# watering_uzin.net
KiCad netlist of a schematic drawn in EAGLE
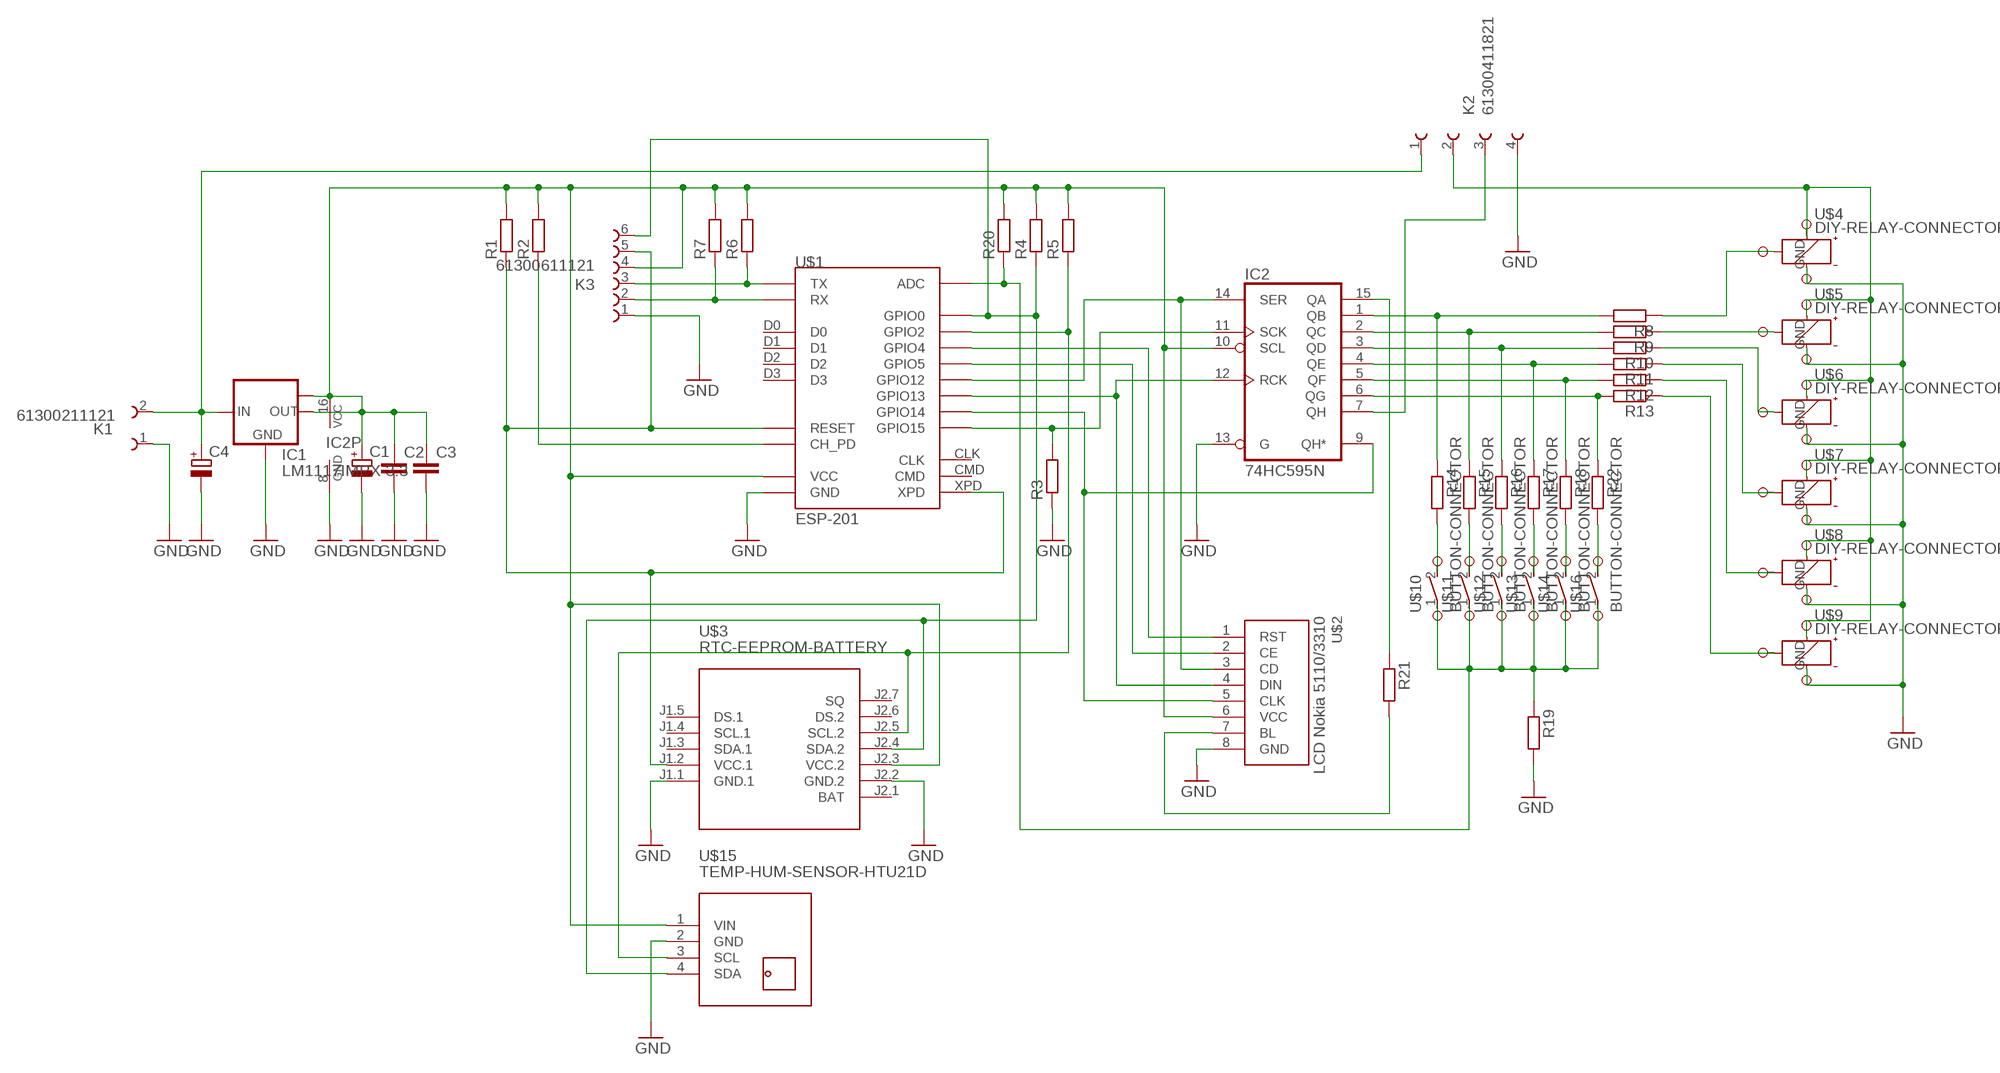
[diagram p0: schematic, sheet 1]

(export (version "E")
  (design (tool "Eeschema 10.0.6"))
  (components
    (comp (ref "C1")
      (value "CPOL-EUSANYO_F13")
      (footprint "eagle-import:SANYO-OSCON_F13")
      (libsource (lib "eagle-import") (part "CPOL-EUSANYO_F13"))
    )
    (comp (ref "C2")
      (value "C-EUC1210")
      (footprint "eagle-import:C1210")
      (libsource (lib "eagle-import") (part "C-EUC1210"))
    )
    (comp (ref "C3")
      (value "C-EUC1210")
      (footprint "eagle-import:C1210")
      (libsource (lib "eagle-import") (part "C-EUC1210"))
    )
    (comp (ref "C4")
      (value "CPOL-EUSANYO_F13")
      (footprint "eagle-import:SANYO-OSCON_F13")
      (libsource (lib "eagle-import") (part "CPOL-EUSANYO_F13"))
    )
    (comp (ref "IC1")
      (value "LM1117IMPX-3.3")
      (footprint "eagle-import:SOT223")
      (libsource (lib "eagle-import") (part "LM1117IMPX-3.3"))
    )
    (comp (ref "IC2")
      (value "74HC595N")
      (footprint "eagle-import:DIL16")
      (libsource (lib "eagle-import") (part "74595NHC"))
    )
    (comp (ref "K1")
      (value "61300211121")
      (footprint "eagle-import:61300211121")
      (libsource (lib "eagle-import") (part "61300211121"))
    )
    (comp (ref "K2")
      (value "61300411821")
      (footprint "eagle-import:61300411821")
      (libsource (lib "eagle-import") (part "61300411821"))
    )
    (comp (ref "K3")
      (value "61300611121")
      (footprint "eagle-import:61300611121")
      (libsource (lib "eagle-import") (part "61300611121"))
    )
    (comp (ref "R1")
      (value "R-EU_R0805")
      (footprint "eagle-import:R0805")
      (libsource (lib "eagle-import") (part "R-EU_R0805"))
    )
    (comp (ref "R2")
      (value "R-EU_R0805")
      (footprint "eagle-import:R0805")
      (libsource (lib "eagle-import") (part "R-EU_R0805"))
    )
    (comp (ref "R3")
      (value "R-EU_R0805")
      (footprint "eagle-import:R0805")
      (libsource (lib "eagle-import") (part "R-EU_R0805"))
    )
    (comp (ref "R4")
      (value "R-EU_R0805")
      (footprint "eagle-import:R0805")
      (libsource (lib "eagle-import") (part "R-EU_R0805"))
    )
    (comp (ref "R5")
      (value "R-EU_R0805")
      (footprint "eagle-import:R0805")
      (libsource (lib "eagle-import") (part "R-EU_R0805"))
    )
    (comp (ref "R6")
      (value "R-EU_R0805")
      (footprint "eagle-import:R0805")
      (libsource (lib "eagle-import") (part "R-EU_R0805"))
    )
    (comp (ref "R7")
      (value "R-EU_R0805")
      (footprint "eagle-import:R0805")
      (libsource (lib "eagle-import") (part "R-EU_R0805"))
    )
    (comp (ref "R8")
      (value "R-EU_R0805")
      (footprint "eagle-import:R0805")
      (libsource (lib "eagle-import") (part "R-EU_R0805"))
    )
    (comp (ref "R9")
      (value "R-EU_R0805")
      (footprint "eagle-import:R0805")
      (libsource (lib "eagle-import") (part "R-EU_R0805"))
    )
    (comp (ref "R10")
      (value "R-EU_R0805")
      (footprint "eagle-import:R0805")
      (libsource (lib "eagle-import") (part "R-EU_R0805"))
    )
    (comp (ref "R11")
      (value "R-EU_R0805")
      (footprint "eagle-import:R0805")
      (libsource (lib "eagle-import") (part "R-EU_R0805"))
    )
    (comp (ref "R12")
      (value "R-EU_R0805")
      (footprint "eagle-import:R0805")
      (libsource (lib "eagle-import") (part "R-EU_R0805"))
    )
    (comp (ref "R13")
      (value "R-EU_R0805")
      (footprint "eagle-import:R0805")
      (libsource (lib "eagle-import") (part "R-EU_R0805"))
    )
    (comp (ref "R14")
      (value "R-EU_R0805")
      (footprint "eagle-import:R0805")
      (libsource (lib "eagle-import") (part "R-EU_R0805"))
    )
    (comp (ref "R15")
      (value "R-EU_R0805")
      (footprint "eagle-import:R0805")
      (libsource (lib "eagle-import") (part "R-EU_R0805"))
    )
    (comp (ref "R16")
      (value "R-EU_R0805")
      (footprint "eagle-import:R0805")
      (libsource (lib "eagle-import") (part "R-EU_R0805"))
    )
    (comp (ref "R17")
      (value "R-EU_R0805")
      (footprint "eagle-import:R0805")
      (libsource (lib "eagle-import") (part "R-EU_R0805"))
    )
    (comp (ref "R18")
      (value "R-EU_R0805")
      (footprint "eagle-import:R0805")
      (libsource (lib "eagle-import") (part "R-EU_R0805"))
    )
    (comp (ref "R19")
      (value "R-EU_R0805")
      (footprint "eagle-import:R0805")
      (libsource (lib "eagle-import") (part "R-EU_R0805"))
    )
    (comp (ref "R20")
      (value "R-EU_R0805")
      (footprint "eagle-import:R0805")
      (libsource (lib "eagle-import") (part "R-EU_R0805"))
    )
    (comp (ref "R21")
      (value "R-EU_R0805")
      (footprint "eagle-import:R0805")
      (libsource (lib "eagle-import") (part "R-EU_R0805"))
    )
    (comp (ref "R22")
      (value "R-EU_R0805")
      (footprint "eagle-import:R0805")
      (libsource (lib "eagle-import") (part "R-EU_R0805"))
    )
    (comp (ref "U$1")
      (value "ESP-201")
      (footprint "eagle-import:ESP-201")
      (libsource (lib "eagle-import") (part "ESP-201"))
    )
    (comp (ref "U$2")
      (value "NOKIA5110")
      (footprint "eagle-import:NOKIA5110")
      (libsource (lib "eagle-import") (part "NOKIA5110"))
    )
    (comp (ref "U$3")
      (value "RTC-EEPROM-BATTERY")
      (footprint "eagle-import:RTC-EEPROM-BATTERY")
      (libsource (lib "eagle-import") (part "RTC-EEPROM-BATTERY"))
    )
    (comp (ref "U$4")
      (value "DIY-RELAY-CONNECTOR")
      (footprint "eagle-import:DIY-RELAY-CONNECTOR")
      (libsource (lib "eagle-import") (part "DIY-RELAY-CONNECTOR"))
    )
    (comp (ref "U$5")
      (value "DIY-RELAY-CONNECTOR")
      (footprint "eagle-import:DIY-RELAY-CONNECTOR")
      (libsource (lib "eagle-import") (part "DIY-RELAY-CONNECTOR"))
    )
    (comp (ref "U$6")
      (value "DIY-RELAY-CONNECTOR")
      (footprint "eagle-import:DIY-RELAY-CONNECTOR")
      (libsource (lib "eagle-import") (part "DIY-RELAY-CONNECTOR"))
    )
    (comp (ref "U$7")
      (value "DIY-RELAY-CONNECTOR")
      (footprint "eagle-import:DIY-RELAY-CONNECTOR")
      (libsource (lib "eagle-import") (part "DIY-RELAY-CONNECTOR"))
    )
    (comp (ref "U$8")
      (value "DIY-RELAY-CONNECTOR")
      (footprint "eagle-import:DIY-RELAY-CONNECTOR")
      (libsource (lib "eagle-import") (part "DIY-RELAY-CONNECTOR"))
    )
    (comp (ref "U$9")
      (value "DIY-RELAY-CONNECTOR")
      (footprint "eagle-import:DIY-RELAY-CONNECTOR")
      (libsource (lib "eagle-import") (part "DIY-RELAY-CONNECTOR"))
    )
    (comp (ref "U$10")
      (value "BUTTON-CONNECTOR")
      (footprint "eagle-import:BUTTON-CONNECTOR")
      (libsource (lib "eagle-import") (part "BUTTON-CONNECTOR"))
    )
    (comp (ref "U$11")
      (value "BUTTON-CONNECTOR")
      (footprint "eagle-import:BUTTON-CONNECTOR")
      (libsource (lib "eagle-import") (part "BUTTON-CONNECTOR"))
    )
    (comp (ref "U$12")
      (value "BUTTON-CONNECTOR")
      (footprint "eagle-import:BUTTON-CONNECTOR")
      (libsource (lib "eagle-import") (part "BUTTON-CONNECTOR"))
    )
    (comp (ref "U$13")
      (value "BUTTON-CONNECTOR")
      (footprint "eagle-import:BUTTON-CONNECTOR")
      (libsource (lib "eagle-import") (part "BUTTON-CONNECTOR"))
    )
    (comp (ref "U$14")
      (value "BUTTON-CONNECTOR")
      (footprint "eagle-import:BUTTON-CONNECTOR")
      (libsource (lib "eagle-import") (part "BUTTON-CONNECTOR"))
    )
    (comp (ref "U$15")
      (value "TEMP-HUM-SENSOR-HTU21D")
      (footprint "eagle-import:TEMP-HUM-SENSOR-HTU21D")
      (libsource (lib "eagle-import") (part "TEMP-HUM-SENSOR-HTU21D"))
    )
    (comp (ref "U$16")
      (value "BUTTON-CONNECTOR")
      (footprint "eagle-import:BUTTON-CONNECTOR")
      (libsource (lib "eagle-import") (part "BUTTON-CONNECTOR"))
    )
  )
  (nets
    (net (code "1") (name "GND") (class "Default")
      (node (ref "C1") (pin "-") (pinfunction "-_-") (pintype "passive"))
      (node (ref "C2") (pin "2") (pinfunction "2_2") (pintype "passive"))
      (node (ref "C3") (pin "2") (pinfunction "2_2") (pintype "passive"))
      (node (ref "C4") (pin "-") (pinfunction "-_-") (pintype "passive"))
      (node (ref "IC1") (pin "1") (pinfunction "GND_1") (pintype "input"))
      (node (ref "IC2") (pin "13") (pinfunction "G_13") (pintype "input"))
      (node (ref "IC2") (pin "8") (pinfunction "GND_8") (pintype "power_in"))
      (node (ref "K1") (pin "1") (pinfunction "1_1") (pintype "passive"))
      (node (ref "K2") (pin "4") (pinfunction "4_4") (pintype "passive"))
      (node (ref "K3") (pin "1") (pinfunction "1_1") (pintype "passive"))
      (node (ref "R19") (pin "2") (pinfunction "2_2") (pintype "passive"))
      (node (ref "R3") (pin "1") (pinfunction "1_1") (pintype "passive"))
      (node (ref "U$1") (pin "GND") (pinfunction "GND_GND") (pintype "bidirectional"))
      (node (ref "U$1") (pin "GND_2") (pinfunction "GND_GND_2") (pintype "bidirectional"))
      (node (ref "U$1") (pin "GND_3") (pinfunction "GND_GND_3") (pintype "bidirectional"))
      (node (ref "U$15") (pin "2") (pinfunction "GND_2") (pintype "power_in"))
      (node (ref "U$2") (pin "8") (pinfunction "GND_8") (pintype "power_in"))
      (node (ref "U$3") (pin "J1.1") (pinfunction "GND.1_J1.1") (pintype "power_in"))
      (node (ref "U$3") (pin "J2.2") (pinfunction "GND.2_J2.2") (pintype "power_in"))
      (node (ref "U$4") (pin "GND") (pinfunction "GND_GND") (pintype "passive"))
      (node (ref "U$5") (pin "GND") (pinfunction "GND_GND") (pintype "passive"))
      (node (ref "U$6") (pin "GND") (pinfunction "GND_GND") (pintype "passive"))
      (node (ref "U$7") (pin "GND") (pinfunction "GND_GND") (pintype "passive"))
      (node (ref "U$8") (pin "GND") (pinfunction "GND_GND") (pintype "passive"))
      (node (ref "U$9") (pin "GND") (pinfunction "GND_GND") (pintype "passive"))
    )
    (net (code "2") (name "Net-(IC1-IN)") (class "Default")
      (node (ref "C4") (pin "+") (pinfunction "+_+") (pintype "passive"))
      (node (ref "IC1") (pin "3") (pinfunction "IN_3") (pintype "input"))
      (node (ref "K1") (pin "2") (pinfunction "2_2") (pintype "passive"))
      (node (ref "K2") (pin "1") (pinfunction "1_1") (pintype "passive"))
    )
    (net (code "3") (name "Net-(IC1-OUT)") (class "Default")
      (node (ref "C1") (pin "+") (pinfunction "+_+") (pintype "passive"))
      (node (ref "C2") (pin "1") (pinfunction "1_1") (pintype "passive"))
      (node (ref "C3") (pin "1") (pinfunction "1_1") (pintype "passive"))
      (node (ref "IC1") (pin "2") (pinfunction "OUT_2") (pintype "passive"))
      (node (ref "IC1") (pin "TAB") (pinfunction "OUT1_TAB") (pintype "passive"))
      (node (ref "IC2") (pin "10") (pinfunction "SCL_10") (pintype "input"))
      (node (ref "IC2") (pin "16") (pinfunction "VCC_16") (pintype "power_in"))
      (node (ref "K3") (pin "4") (pinfunction "4_4") (pintype "passive"))
      (node (ref "R1") (pin "2") (pinfunction "2_2") (pintype "passive"))
      (node (ref "R2") (pin "2") (pinfunction "2_2") (pintype "passive"))
      (node (ref "R20") (pin "2") (pinfunction "2_2") (pintype "passive"))
      (node (ref "R4") (pin "2") (pinfunction "2_2") (pintype "passive"))
      (node (ref "R5") (pin "2") (pinfunction "2_2") (pintype "passive"))
      (node (ref "R6") (pin "2") (pinfunction "2_2") (pintype "passive"))
      (node (ref "R7") (pin "2") (pinfunction "2_2") (pintype "passive"))
      (node (ref "U$1") (pin "3V3") (pinfunction "VCC_3V3") (pintype "bidirectional"))
      (node (ref "U$1") (pin "3V3_2") (pinfunction "VCC_3V3_2") (pintype "bidirectional"))
      (node (ref "U$1") (pin "3V3_3") (pinfunction "VCC_3V3_3") (pintype "bidirectional"))
      (node (ref "U$15") (pin "1") (pinfunction "VIN_1") (pintype "power_in"))
      (node (ref "U$2") (pin "6") (pinfunction "VCC_6") (pintype "power_in"))
      (node (ref "U$3") (pin "J2.3") (pinfunction "VCC.2_J2.3") (pintype "power_in"))
    )
    (net (code "4") (name "Net-(IC2A-QA)") (class "Default")
      (node (ref "IC2") (pin "15") (pinfunction "QA_15") (pintype "tri_state"))
      (node (ref "R21") (pin "1") (pinfunction "1_1") (pintype "passive"))
    )
    (net (code "5") (name "Net-(IC2A-QB)") (class "Default")
      (node (ref "IC2") (pin "1") (pinfunction "QB_1") (pintype "tri_state"))
      (node (ref "R14") (pin "1") (pinfunction "1_1") (pintype "passive"))
      (node (ref "R8") (pin "2") (pinfunction "2_2") (pintype "passive"))
    )
    (net (code "6") (name "Net-(IC2A-QC)") (class "Default")
      (node (ref "IC2") (pin "2") (pinfunction "QC_2") (pintype "tri_state"))
      (node (ref "R15") (pin "1") (pinfunction "1_1") (pintype "passive"))
      (node (ref "R9") (pin "2") (pinfunction "2_2") (pintype "passive"))
    )
    (net (code "7") (name "Net-(IC2A-QD)") (class "Default")
      (node (ref "IC2") (pin "3") (pinfunction "QD_3") (pintype "tri_state"))
      (node (ref "R10") (pin "2") (pinfunction "2_2") (pintype "passive"))
      (node (ref "R16") (pin "1") (pinfunction "1_1") (pintype "passive"))
    )
    (net (code "8") (name "Net-(IC2A-QE)") (class "Default")
      (node (ref "IC2") (pin "4") (pinfunction "QE_4") (pintype "tri_state"))
      (node (ref "R11") (pin "2") (pinfunction "2_2") (pintype "passive"))
      (node (ref "R17") (pin "1") (pinfunction "1_1") (pintype "passive"))
    )
    (net (code "9") (name "Net-(IC2A-QF)") (class "Default")
      (node (ref "IC2") (pin "5") (pinfunction "QF_5") (pintype "tri_state"))
      (node (ref "R12") (pin "2") (pinfunction "2_2") (pintype "passive"))
      (node (ref "R18") (pin "1") (pinfunction "1_1") (pintype "passive"))
    )
    (net (code "10") (name "Net-(IC2A-QG)") (class "Default")
      (node (ref "IC2") (pin "6") (pinfunction "QG_6") (pintype "tri_state"))
      (node (ref "R13") (pin "2") (pinfunction "2_2") (pintype "passive"))
      (node (ref "R22") (pin "1") (pinfunction "1_1") (pintype "passive"))
    )
    (net (code "11") (name "Net-(IC2A-QH)") (class "Default")
      (node (ref "IC2") (pin "7") (pinfunction "QH_7") (pintype "tri_state"))
      (node (ref "K2") (pin "3") (pinfunction "3_3") (pintype "passive"))
    )
    (net (code "12") (name "Net-(IC2A-QH*)") (class "Default")
      (node (ref "IC2") (pin "9") (pinfunction "QH*_9") (pintype "tri_state"))
      (node (ref "U$1") (pin "GPIO14") (pinfunction "GPIO14_GPIO14") (pintype "bidirectional"))
      (node (ref "U$2") (pin "5") (pinfunction "CLK_5") (pintype "bidirectional"))
    )
    (net (code "13") (name "Net-(IC2A-RCK)") (class "Default")
      (node (ref "IC2") (pin "12") (pinfunction "RCK_12") (pintype "input"))
      (node (ref "U$1") (pin "GPIO13") (pinfunction "GPIO13_GPIO13") (pintype "bidirectional"))
      (node (ref "U$2") (pin "4") (pinfunction "DIN_4") (pintype "bidirectional"))
    )
    (net (code "14") (name "Net-(IC2A-SCK)") (class "Default")
      (node (ref "IC2") (pin "11") (pinfunction "SCK_11") (pintype "input"))
      (node (ref "R3") (pin "2") (pinfunction "2_2") (pintype "passive"))
      (node (ref "U$1") (pin "GPIO15") (pinfunction "GPIO15_GPIO15") (pintype "bidirectional"))
    )
    (net (code "15") (name "Net-(IC2A-SER)") (class "Default")
      (node (ref "IC2") (pin "14") (pinfunction "SER_14") (pintype "input"))
      (node (ref "U$1") (pin "GPIO12") (pinfunction "GPIO12_GPIO12") (pintype "bidirectional"))
      (node (ref "U$2") (pin "3") (pinfunction "CD_3") (pintype "bidirectional"))
    )
    (net (code "16") (name "Net-(K2-Pad2)") (class "Default")
      (node (ref "K2") (pin "2") (pinfunction "2_2") (pintype "passive"))
      (node (ref "U$4") (pin "VCC") (pinfunction "VCC_VCC") (pintype "passive"))
      (node (ref "U$5") (pin "VCC") (pinfunction "VCC_VCC") (pintype "passive"))
      (node (ref "U$6") (pin "VCC") (pinfunction "VCC_VCC") (pintype "passive"))
      (node (ref "U$7") (pin "VCC") (pinfunction "VCC_VCC") (pintype "passive"))
      (node (ref "U$8") (pin "VCC") (pinfunction "VCC_VCC") (pintype "passive"))
      (node (ref "U$9") (pin "VCC") (pinfunction "VCC_VCC") (pintype "passive"))
    )
    (net (code "17") (name "Net-(K3-Pad2)") (class "Default")
      (node (ref "K3") (pin "2") (pinfunction "2_2") (pintype "passive"))
      (node (ref "R7") (pin "1") (pinfunction "1_1") (pintype "passive"))
      (node (ref "U$1") (pin "RX") (pinfunction "RX_RX") (pintype "bidirectional"))
    )
    (net (code "18") (name "Net-(K3-Pad3)") (class "Default")
      (node (ref "K3") (pin "3") (pinfunction "3_3") (pintype "passive"))
      (node (ref "R6") (pin "1") (pinfunction "1_1") (pintype "passive"))
      (node (ref "U$1") (pin "TX") (pinfunction "TX_TX") (pintype "bidirectional"))
    )
    (net (code "19") (name "Net-(R2-Pad1)") (class "Default")
      (node (ref "R2") (pin "1") (pinfunction "1_1") (pintype "passive"))
      (node (ref "U$1") (pin "CH_PD") (pinfunction "CH_PD_CH_PD") (pintype "bidirectional"))
    )
    (net (code "20") (name "Net-(R8-Pad1)") (class "Default")
      (node (ref "R8") (pin "1") (pinfunction "1_1") (pintype "passive"))
      (node (ref "U$4") (pin "IN") (pinfunction "IN_IN") (pintype "passive"))
    )
    (net (code "21") (name "Net-(R9-Pad1)") (class "Default")
      (node (ref "R9") (pin "1") (pinfunction "1_1") (pintype "passive"))
      (node (ref "U$5") (pin "IN") (pinfunction "IN_IN") (pintype "passive"))
    )
    (net (code "22") (name "Net-(R10-Pad1)") (class "Default")
      (node (ref "R10") (pin "1") (pinfunction "1_1") (pintype "passive"))
      (node (ref "U$6") (pin "IN") (pinfunction "IN_IN") (pintype "passive"))
    )
    (net (code "23") (name "Net-(R11-Pad1)") (class "Default")
      (node (ref "R11") (pin "1") (pinfunction "1_1") (pintype "passive"))
      (node (ref "U$7") (pin "IN") (pinfunction "IN_IN") (pintype "passive"))
    )
    (net (code "24") (name "Net-(R12-Pad1)") (class "Default")
      (node (ref "R12") (pin "1") (pinfunction "1_1") (pintype "passive"))
      (node (ref "U$8") (pin "IN") (pinfunction "IN_IN") (pintype "passive"))
    )
    (net (code "25") (name "Net-(R13-Pad1)") (class "Default")
      (node (ref "R13") (pin "1") (pinfunction "1_1") (pintype "passive"))
      (node (ref "U$9") (pin "IN") (pinfunction "IN_IN") (pintype "passive"))
    )
    (net (code "26") (name "Net-(U$1-RESET)") (class "Default")
      (node (ref "K3") (pin "5") (pinfunction "5_5") (pintype "passive"))
      (node (ref "R1") (pin "1") (pinfunction "1_1") (pintype "passive"))
      (node (ref "U$1") (pin "RST") (pinfunction "RESET_RST") (pintype "bidirectional"))
      (node (ref "U$1") (pin "XPD") (pinfunction "XPD_XPD") (pintype "bidirectional"))
      (node (ref "U$3") (pin "J1.2") (pinfunction "VCC.1_J1.2") (pintype "power_in"))
    )
    (net (code "27") (name "Net-(U$2-BL)") (class "Default")
      (node (ref "R21") (pin "2") (pinfunction "2_2") (pintype "passive"))
      (node (ref "U$2") (pin "7") (pinfunction "BL_7") (pintype "bidirectional"))
    )
    (net (code "28") (name "Net-(U$2-CE)") (class "Default")
      (node (ref "U$1") (pin "GPIO5") (pinfunction "GPIO5_GPIO5") (pintype "bidirectional"))
      (node (ref "U$2") (pin "2") (pinfunction "CE_2") (pintype "bidirectional"))
    )
    (net (code "29") (name "Net-(U$2-RST)") (class "Default")
      (node (ref "U$1") (pin "GPIO4") (pinfunction "GPIO4_GPIO4") (pintype "bidirectional"))
      (node (ref "U$2") (pin "1") (pinfunction "RST_1") (pintype "bidirectional"))
    )
    (net (code "30") (name "Net-(U$10-P)") (class "Default")
      (node (ref "R19") (pin "1") (pinfunction "1_1") (pintype "passive"))
      (node (ref "R20") (pin "1") (pinfunction "1_1") (pintype "passive"))
      (node (ref "U$1") (pin "ADC") (pinfunction "ADC_ADC") (pintype "bidirectional"))
      (node (ref "U$10") (pin "1") (pinfunction "P_1") (pintype "passive"))
      (node (ref "U$11") (pin "1") (pinfunction "P_1") (pintype "passive"))
      (node (ref "U$12") (pin "1") (pinfunction "P_1") (pintype "passive"))
      (node (ref "U$13") (pin "1") (pinfunction "P_1") (pintype "passive"))
      (node (ref "U$14") (pin "1") (pinfunction "P_1") (pintype "passive"))
      (node (ref "U$16") (pin "1") (pinfunction "P_1") (pintype "passive"))
    )
    (net (code "31") (name "Net-(U$10-S)") (class "Default")
      (node (ref "R14") (pin "2") (pinfunction "2_2") (pintype "passive"))
      (node (ref "U$10") (pin "2") (pinfunction "S_2") (pintype "passive"))
    )
    (net (code "32") (name "Net-(U$11-S)") (class "Default")
      (node (ref "R15") (pin "2") (pinfunction "2_2") (pintype "passive"))
      (node (ref "U$11") (pin "2") (pinfunction "S_2") (pintype "passive"))
    )
    (net (code "33") (name "Net-(U$12-S)") (class "Default")
      (node (ref "R16") (pin "2") (pinfunction "2_2") (pintype "passive"))
      (node (ref "U$12") (pin "2") (pinfunction "S_2") (pintype "passive"))
    )
    (net (code "34") (name "Net-(U$13-S)") (class "Default")
      (node (ref "R17") (pin "2") (pinfunction "2_2") (pintype "passive"))
      (node (ref "U$13") (pin "2") (pinfunction "S_2") (pintype "passive"))
    )
    (net (code "35") (name "Net-(U$14-S)") (class "Default")
      (node (ref "R18") (pin "2") (pinfunction "2_2") (pintype "passive"))
      (node (ref "U$14") (pin "2") (pinfunction "S_2") (pintype "passive"))
    )
    (net (code "36") (name "Net-(U$15-SCL)") (class "Default")
      (node (ref "R5") (pin "1") (pinfunction "1_1") (pintype "passive"))
      (node (ref "U$1") (pin "GPIO2") (pinfunction "GPIO2_GPIO2") (pintype "bidirectional"))
      (node (ref "U$15") (pin "3") (pinfunction "SCL_3") (pintype "bidirectional"))
      (node (ref "U$3") (pin "J2.5") (pinfunction "SCL.2_J2.5") (pintype "bidirectional"))
    )
    (net (code "37") (name "Net-(U$15-SDA)") (class "Default")
      (node (ref "K3") (pin "6") (pinfunction "6_6") (pintype "passive"))
      (node (ref "R4") (pin "1") (pinfunction "1_1") (pintype "passive"))
      (node (ref "U$1") (pin "GPIO0") (pinfunction "GPIO0_GPIO0") (pintype "bidirectional"))
      (node (ref "U$15") (pin "4") (pinfunction "SDA_4") (pintype "bidirectional"))
      (node (ref "U$3") (pin "J2.4") (pinfunction "SDA.2_J2.4") (pintype "bidirectional"))
    )
    (net (code "38") (name "Net-(U$16-S)") (class "Default")
      (node (ref "R22") (pin "2") (pinfunction "2_2") (pintype "passive"))
      (node (ref "U$16") (pin "2") (pinfunction "S_2") (pintype "passive"))
    )
    (net (code "39") (name "unconnected-(U$1-PadCLK)") (class "Default")
      (node (ref "U$1") (pin "CLK") (pinfunction "CLK_CLK") (pintype "bidirectional"))
    )
    (net (code "40") (name "unconnected-(U$1-PadCMD)") (class "Default")
      (node (ref "U$1") (pin "CMD") (pinfunction "CMD_CMD") (pintype "bidirectional"))
    )
    (net (code "41") (name "unconnected-(U$1-PadD0)") (class "Default")
      (node (ref "U$1") (pin "D0") (pinfunction "D0_D0") (pintype "bidirectional"))
    )
    (net (code "42") (name "unconnected-(U$1-PadD1)") (class "Default")
      (node (ref "U$1") (pin "D1") (pinfunction "D1_D1") (pintype "bidirectional"))
    )
    (net (code "43") (name "unconnected-(U$1-PadD2)") (class "Default")
      (node (ref "U$1") (pin "D2") (pinfunction "D2_D2") (pintype "bidirectional"))
    )
    (net (code "44") (name "unconnected-(U$1-PadD3)") (class "Default")
      (node (ref "U$1") (pin "D3") (pinfunction "D3_D3") (pintype "bidirectional"))
    )
    (net (code "45") (name "unconnected-(U$3-BAT-PadJ2.1)") (class "Default")
      (node (ref "U$3") (pin "J2.1") (pinfunction "BAT_J2.1") (pintype "bidirectional"))
    )
    (net (code "46") (name "unconnected-(U$3-DS.1-PadJ1.5)") (class "Default")
      (node (ref "U$3") (pin "J1.5") (pinfunction "DS.1_J1.5") (pintype "bidirectional"))
    )
    (net (code "47") (name "unconnected-(U$3-DS.2-PadJ2.6)") (class "Default")
      (node (ref "U$3") (pin "J2.6") (pinfunction "DS.2_J2.6") (pintype "bidirectional"))
    )
    (net (code "48") (name "unconnected-(U$3-SCL.1-PadJ1.4)") (class "Default")
      (node (ref "U$3") (pin "J1.4") (pinfunction "SCL.1_J1.4") (pintype "bidirectional"))
    )
    (net (code "49") (name "unconnected-(U$3-SDA.1-PadJ1.3)") (class "Default")
      (node (ref "U$3") (pin "J1.3") (pinfunction "SDA.1_J1.3") (pintype "bidirectional"))
    )
    (net (code "50") (name "unconnected-(U$3-SQ-PadJ2.7)") (class "Default")
      (node (ref "U$3") (pin "J2.7") (pinfunction "SQ_J2.7") (pintype "bidirectional"))
    )
  )
)
